# VisualightMicroDIY_036_gnd.net
KiCad netlist of a schematic drawn in EAGLE
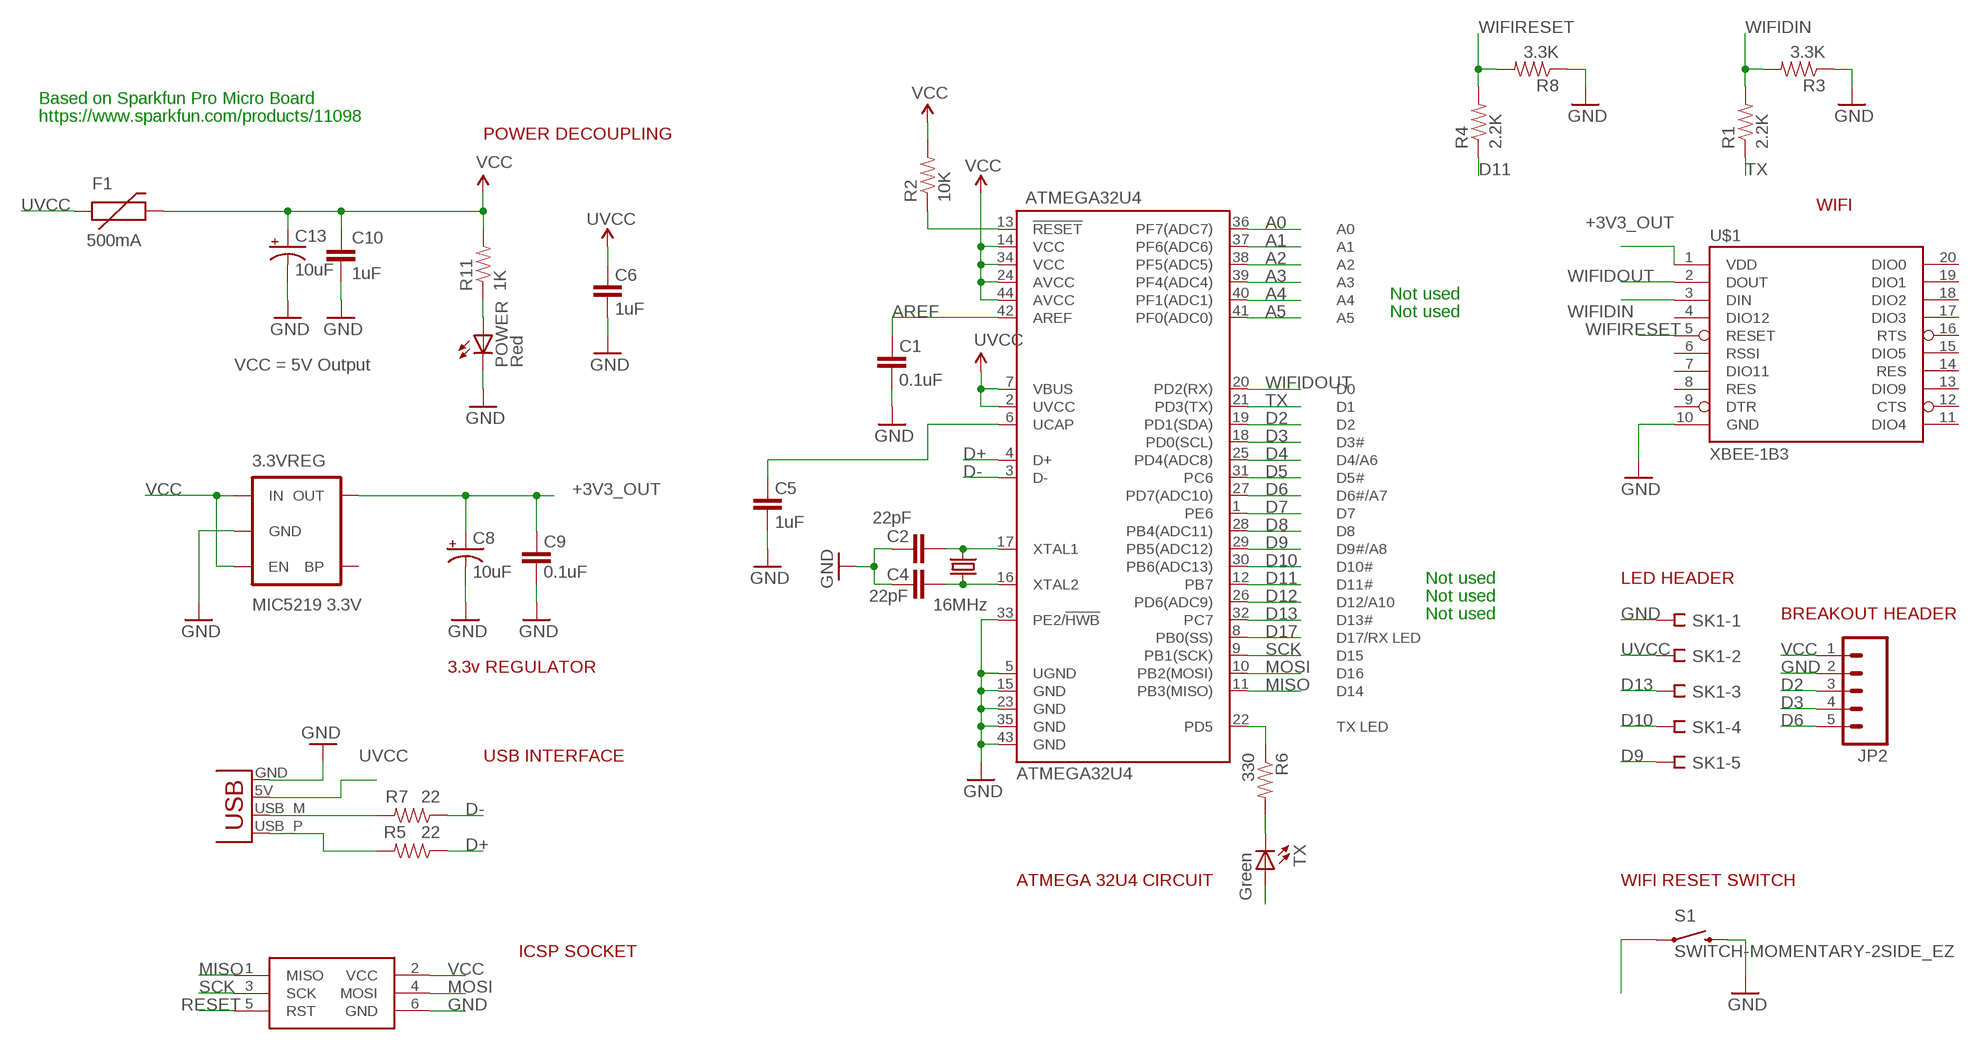
[diagram p0: schematic, sheet 1]

(export (version "E")
  (design (tool "Eeschema 10.0.6"))
  (components
    (comp (ref "3.3VREG")
      (value "MIC5219 3.3V")
      (footprint "eagle-import:SOT23-5")
      (libsource (lib "eagle-import") (part "V_REG_MIC52193.3V"))
    )
    (comp (ref "ATMEGA32U4")
      (value "ATMEGA32U4")
      (footprint "eagle-import:SPARKFUN-DIGITALIC_TQFP44")
      (libsource (lib "eagle-import") (part "ATMEGA32U4TQFP"))
    )
    (comp (ref "C1")
      (value "0.1uF")
      (footprint "eagle-import:0402-CAP")
      (libsource (lib "eagle-import") (part "CAP0402-CAP"))
    )
    (comp (ref "C2")
      (value "22pF")
      (footprint "eagle-import:0402-CAP")
      (libsource (lib "eagle-import") (part "CAP0402-CAP"))
    )
    (comp (ref "C4")
      (value "22pF")
      (footprint "eagle-import:0402-CAP")
      (libsource (lib "eagle-import") (part "CAP0402-CAP"))
    )
    (comp (ref "C5")
      (value "1uF")
      (footprint "eagle-import:0402-CAP")
      (libsource (lib "eagle-import") (part "CAP0402-CAP"))
    )
    (comp (ref "C6")
      (value "1uF")
      (footprint "eagle-import:0402-CAP")
      (libsource (lib "eagle-import") (part "CAP0402-CAP"))
    )
    (comp (ref "C8")
      (value "10uF")
      (footprint "eagle-import:EIA3216")
      (libsource (lib "eagle-import") (part "CAP_POL1206"))
    )
    (comp (ref "C9")
      (value "0.1uF")
      (footprint "eagle-import:0402-CAP")
      (libsource (lib "eagle-import") (part "CAP0402-CAP"))
    )
    (comp (ref "C10")
      (value "1uF")
      (footprint "eagle-import:0402-CAP")
      (libsource (lib "eagle-import") (part "CAP0402-CAP"))
    )
    (comp (ref "C13")
      (value "10uF")
      (footprint "eagle-import:EIA3216")
      (libsource (lib "eagle-import") (part "CAP_POL1206"))
    )
    (comp (ref "F1")
      (value "500mA")
      (footprint "eagle-import:PTC-1206")
      (libsource (lib "eagle-import") (part "PTCSMD"))
    )
    (comp (ref "ISP1")
      (value "AVRISP-6")
      (footprint "eagle-import:AVRISP")
      (libsource (lib "eagle-import") (part "AVRISP-6"))
    )
    (comp (ref "JP2")
      (value "M05PTH")
      (footprint "eagle-import:1X05")
      (libsource (lib "eagle-import") (part "M05PTH"))
    )
    (comp (ref "POWER")
      (value "Red")
      (footprint "eagle-import:LED-0603")
      (libsource (lib "eagle-import") (part "LED0603"))
    )
    (comp (ref "R1")
      (value "2.2K")
      (footprint "eagle-import:0402-RES")
      (libsource (lib "eagle-import") (part "RESISTOR0402-RES"))
    )
    (comp (ref "R2")
      (value "10K")
      (footprint "eagle-import:0402-RES")
      (libsource (lib "eagle-import") (part "RESISTOR0402-RES"))
    )
    (comp (ref "R3")
      (value "3.3K")
      (footprint "eagle-import:0402-RES")
      (libsource (lib "eagle-import") (part "RESISTOR0402-RES"))
    )
    (comp (ref "R4")
      (value "2.2K")
      (footprint "eagle-import:0402-RES")
      (libsource (lib "eagle-import") (part "RESISTOR0402-RES"))
    )
    (comp (ref "R5")
      (value "22")
      (footprint "eagle-import:0402-RES")
      (libsource (lib "eagle-import") (part "RESISTOR0402-RES"))
    )
    (comp (ref "R6")
      (value "330")
      (footprint "eagle-import:0402-RES")
      (libsource (lib "eagle-import") (part "RESISTOR0402-RES"))
    )
    (comp (ref "R7")
      (value "22")
      (footprint "eagle-import:0402-RES")
      (libsource (lib "eagle-import") (part "RESISTOR0402-RES"))
    )
    (comp (ref "R8")
      (value "3.3K")
      (footprint "eagle-import:0402-RES")
      (libsource (lib "eagle-import") (part "RESISTOR0402-RES"))
    )
    (comp (ref "R11")
      (value "1K")
      (footprint "eagle-import:0402-RES")
      (libsource (lib "eagle-import") (part "RESISTOR0402-RES"))
    )
    (comp (ref "S1")
      (value "SWITCH-MOMENTARY-2SIDE_EZ")
      (footprint "eagle-import:TACTILE-PTH-SIDEEZ")
      (libsource (lib "eagle-import") (part "SWITCH-MOMENTARY-2SIDE_EZ"))
    )
    (comp (ref "SK1")
      (value "DF3-05S")
      (footprint "eagle-import:DF3S-05")
      (libsource (lib "eagle-import") (part "DF3-05S"))
    )
    (comp (ref "TX")
      (value "Green")
      (footprint "eagle-import:LED-0603")
      (libsource (lib "eagle-import") (part "LED0603"))
    )
    (comp (ref "U$1")
      (value "XBEE-1B3")
      (footprint "eagle-import:XBEE-SMD")
      (libsource (lib "eagle-import") (part "XBEE-1B3"))
    )
    (comp (ref "X2")
      (value "USBPCB")
      (footprint "eagle-import:USB-A-PCB")
      (libsource (lib "eagle-import") (part "USBPCB"))
    )
    (comp (ref "Y1")
      (value "16MHz")
      (footprint "eagle-import:CRYSTAL-SMD-5X3")
      (libsource (lib "eagle-import") (part "CRYSTAL5X3"))
    )
  )
  (nets
    (net (code "1") (name "/+3V3_OUT") (class "Default")
      (node (ref "3.3VREG") (pin "5") (pinfunction "OUT_5") (pintype "passive"))
      (node (ref "C8") (pin "A") (pinfunction "+_A") (pintype "passive"))
      (node (ref "C9") (pin "2") (pinfunction "2_2") (pintype "passive"))
      (node (ref "U$1") (pin "1") (pinfunction "VDD_1") (pintype "power_in"))
    )
    (net (code "2") (name "/A0") (class "Default")
      (node (ref "ATMEGA32U4") (pin "36") (pinfunction "PF7(ADC7)_36") (pintype "bidirectional"))
    )
    (net (code "3") (name "/A1") (class "Default")
      (node (ref "ATMEGA32U4") (pin "37") (pinfunction "PF6(ADC6)_37") (pintype "bidirectional"))
    )
    (net (code "4") (name "/A2") (class "Default")
      (node (ref "ATMEGA32U4") (pin "38") (pinfunction "PF5(ADC5)_38") (pintype "bidirectional"))
    )
    (net (code "5") (name "/A3") (class "Default")
      (node (ref "ATMEGA32U4") (pin "39") (pinfunction "PF4(ADC4)_39") (pintype "bidirectional"))
    )
    (net (code "6") (name "/A4") (class "Default")
      (node (ref "ATMEGA32U4") (pin "40") (pinfunction "PF1(ADC1)_40") (pintype "bidirectional"))
    )
    (net (code "7") (name "/A5") (class "Default")
      (node (ref "ATMEGA32U4") (pin "41") (pinfunction "PF0(ADC0)_41") (pintype "bidirectional"))
    )
    (net (code "8") (name "/AREF") (class "Default")
      (node (ref "ATMEGA32U4") (pin "42") (pinfunction "AREF_42") (pintype "bidirectional"))
      (node (ref "C1") (pin "2") (pinfunction "2_2") (pintype "passive"))
    )
    (net (code "9") (name "/D+") (class "Default")
      (node (ref "ATMEGA32U4") (pin "4") (pinfunction "D+_4") (pintype "bidirectional"))
      (node (ref "R5") (pin "1") (pinfunction "1_1") (pintype "passive"))
    )
    (net (code "10") (name "/D-") (class "Default")
      (node (ref "ATMEGA32U4") (pin "3") (pinfunction "D-_3") (pintype "bidirectional"))
      (node (ref "R7") (pin "1") (pinfunction "1_1") (pintype "passive"))
    )
    (net (code "11") (name "/D2") (class "Default")
      (node (ref "ATMEGA32U4") (pin "19") (pinfunction "PD1(SDA)_19") (pintype "bidirectional"))
      (node (ref "JP2") (pin "3") (pinfunction "3_3") (pintype "passive"))
    )
    (net (code "12") (name "/D3") (class "Default")
      (node (ref "ATMEGA32U4") (pin "18") (pinfunction "PD0(SCL)_18") (pintype "bidirectional"))
      (node (ref "JP2") (pin "4") (pinfunction "4_4") (pintype "passive"))
    )
    (net (code "13") (name "/D4") (class "Default")
      (node (ref "ATMEGA32U4") (pin "25") (pinfunction "PD4(ADC8)_25") (pintype "bidirectional"))
    )
    (net (code "14") (name "/D5") (class "Default")
      (node (ref "ATMEGA32U4") (pin "31") (pinfunction "PC6_31") (pintype "bidirectional"))
    )
    (net (code "15") (name "/D6") (class "Default")
      (node (ref "ATMEGA32U4") (pin "27") (pinfunction "PD7(ADC10)_27") (pintype "bidirectional"))
      (node (ref "JP2") (pin "5") (pinfunction "5_5") (pintype "passive"))
    )
    (net (code "16") (name "/D7") (class "Default")
      (node (ref "ATMEGA32U4") (pin "1") (pinfunction "PE6_1") (pintype "bidirectional"))
      (node (ref "S1") (pin "1") (pinfunction "1_1") (pintype "passive"))
    )
    (net (code "17") (name "/D8") (class "Default")
      (node (ref "ATMEGA32U4") (pin "28") (pinfunction "PB4(ADC11)_28") (pintype "bidirectional"))
    )
    (net (code "18") (name "/D9") (class "Default")
      (node (ref "ATMEGA32U4") (pin "29") (pinfunction "PB5(ADC12)_29") (pintype "bidirectional"))
      (node (ref "SK1") (pin "5") (pinfunction "S_5") (pintype "passive"))
    )
    (net (code "19") (name "/D10") (class "Default")
      (node (ref "ATMEGA32U4") (pin "30") (pinfunction "PB6(ADC13)_30") (pintype "bidirectional"))
      (node (ref "SK1") (pin "4") (pinfunction "S_4") (pintype "passive"))
    )
    (net (code "20") (name "/D11") (class "Default")
      (node (ref "ATMEGA32U4") (pin "12") (pinfunction "PB7_12") (pintype "bidirectional"))
      (node (ref "R4") (pin "1") (pinfunction "1_1") (pintype "passive"))
    )
    (net (code "21") (name "/D12") (class "Default")
      (node (ref "ATMEGA32U4") (pin "26") (pinfunction "PD6(ADC9)_26") (pintype "bidirectional"))
    )
    (net (code "22") (name "/D13") (class "Default")
      (node (ref "ATMEGA32U4") (pin "32") (pinfunction "PC7_32") (pintype "bidirectional"))
      (node (ref "SK1") (pin "3") (pinfunction "S_3") (pintype "passive"))
    )
    (net (code "23") (name "/D17") (class "Default")
      (node (ref "ATMEGA32U4") (pin "8") (pinfunction "PB0(SS)_8") (pintype "bidirectional"))
    )
    (net (code "24") (name "/MISO") (class "Default")
      (node (ref "ATMEGA32U4") (pin "11") (pinfunction "PB3(MISO)_11") (pintype "bidirectional"))
      (node (ref "ISP1") (pin "1") (pinfunction "MISO_1") (pintype "input"))
    )
    (net (code "25") (name "/MOSI") (class "Default")
      (node (ref "ATMEGA32U4") (pin "10") (pinfunction "PB2(MOSI)_10") (pintype "bidirectional"))
      (node (ref "ISP1") (pin "4") (pinfunction "MOSI_4") (pintype "output"))
    )
    (net (code "26") (name "/RESET") (class "Default")
      (node (ref "ATMEGA32U4") (pin "13") (pinfunction "~{RESET}_13") (pintype "bidirectional"))
      (node (ref "ISP1") (pin "5") (pinfunction "RST_5") (pintype "output"))
      (node (ref "R2") (pin "1") (pinfunction "1_1") (pintype "passive"))
    )
    (net (code "27") (name "/SCK") (class "Default")
      (node (ref "ATMEGA32U4") (pin "9") (pinfunction "PB1(SCK)_9") (pintype "bidirectional"))
      (node (ref "ISP1") (pin "3") (pinfunction "SCK_3") (pintype "output"))
    )
    (net (code "28") (name "/TX") (class "Default")
      (node (ref "ATMEGA32U4") (pin "21") (pinfunction "PD3(TX)_21") (pintype "bidirectional"))
      (node (ref "R1") (pin "1") (pinfunction "1_1") (pintype "passive"))
    )
    (net (code "29") (name "/WIFIDIN") (class "Default")
      (node (ref "R1") (pin "2") (pinfunction "2_2") (pintype "passive"))
      (node (ref "R3") (pin "2") (pinfunction "2_2") (pintype "passive"))
      (node (ref "U$1") (pin "3") (pinfunction "DIN_3") (pintype "input"))
    )
    (net (code "30") (name "/WIFIDOUT") (class "Default")
      (node (ref "ATMEGA32U4") (pin "20") (pinfunction "PD2(RX)_20") (pintype "bidirectional"))
      (node (ref "U$1") (pin "2") (pinfunction "DOUT_2") (pintype "output"))
    )
    (net (code "31") (name "/WIFIRESET") (class "Default")
      (node (ref "R4") (pin "2") (pinfunction "2_2") (pintype "passive"))
      (node (ref "R8") (pin "2") (pinfunction "2_2") (pintype "passive"))
      (node (ref "U$1") (pin "5") (pinfunction "RESET_5") (pintype "input"))
    )
    (net (code "32") (name "GND") (class "Default")
      (node (ref "3.3VREG") (pin "2") (pinfunction "GND_2") (pintype "input"))
      (node (ref "ATMEGA32U4") (pin "15") (pinfunction "GND_15") (pintype "bidirectional"))
      (node (ref "ATMEGA32U4") (pin "23") (pinfunction "GND_23") (pintype "bidirectional"))
      (node (ref "ATMEGA32U4") (pin "33") (pinfunction "PE2/~{HWB}_33") (pintype "bidirectional"))
      (node (ref "ATMEGA32U4") (pin "35") (pinfunction "GND_35") (pintype "bidirectional"))
      (node (ref "ATMEGA32U4") (pin "43") (pinfunction "GND_43") (pintype "bidirectional"))
      (node (ref "ATMEGA32U4") (pin "5") (pinfunction "UGND_5") (pintype "bidirectional"))
      (node (ref "C1") (pin "1") (pinfunction "1_1") (pintype "passive"))
      (node (ref "C10") (pin "2") (pinfunction "2_2") (pintype "passive"))
      (node (ref "C13") (pin "C") (pinfunction "-_C") (pintype "passive"))
      (node (ref "C2") (pin "2") (pinfunction "2_2") (pintype "passive"))
      (node (ref "C4") (pin "2") (pinfunction "2_2") (pintype "passive"))
      (node (ref "C5") (pin "1") (pinfunction "1_1") (pintype "passive"))
      (node (ref "C6") (pin "1") (pinfunction "1_1") (pintype "passive"))
      (node (ref "C8") (pin "C") (pinfunction "-_C") (pintype "passive"))
      (node (ref "C9") (pin "1") (pinfunction "1_1") (pintype "passive"))
      (node (ref "ISP1") (pin "6") (pinfunction "GND_6") (pintype "power_in"))
      (node (ref "JP2") (pin "2") (pinfunction "2_2") (pintype "passive"))
      (node (ref "POWER") (pin "C") (pinfunction "C_C") (pintype "passive"))
      (node (ref "R3") (pin "1") (pinfunction "1_1") (pintype "passive"))
      (node (ref "R8") (pin "1") (pinfunction "1_1") (pintype "passive"))
      (node (ref "S1") (pin "2") (pinfunction "2_2") (pintype "passive"))
      (node (ref "SK1") (pin "1") (pinfunction "S_1") (pintype "passive"))
      (node (ref "U$1") (pin "10") (pinfunction "GND_10") (pintype "power_in"))
      (node (ref "X2") (pin "GND") (pinfunction "GND_GND") (pintype "bidirectional"))
    )
    (net (code "33") (name "Net-(ATMEGA32U4-PD5)") (class "Default")
      (node (ref "ATMEGA32U4") (pin "22") (pinfunction "PD5_22") (pintype "bidirectional"))
      (node (ref "R6") (pin "1") (pinfunction "1_1") (pintype "passive"))
    )
    (net (code "34") (name "Net-(ATMEGA32U4-UCAP)") (class "Default")
      (node (ref "ATMEGA32U4") (pin "6") (pinfunction "UCAP_6") (pintype "bidirectional"))
      (node (ref "C5") (pin "2") (pinfunction "2_2") (pintype "passive"))
    )
    (net (code "35") (name "Net-(ATMEGA32U4-XTAL1)") (class "Default")
      (node (ref "ATMEGA32U4") (pin "17") (pinfunction "XTAL1_17") (pintype "bidirectional"))
      (node (ref "C2") (pin "1") (pinfunction "1_1") (pintype "passive"))
      (node (ref "Y1") (pin "3") (pinfunction "2_3") (pintype "passive"))
    )
    (net (code "36") (name "Net-(ATMEGA32U4-XTAL2)") (class "Default")
      (node (ref "ATMEGA32U4") (pin "16") (pinfunction "XTAL2_16") (pintype "bidirectional"))
      (node (ref "C4") (pin "1") (pinfunction "1_1") (pintype "passive"))
      (node (ref "Y1") (pin "1") (pinfunction "1_1") (pintype "passive"))
    )
    (net (code "37") (name "Net-(POWER-PadA)") (class "Default")
      (node (ref "POWER") (pin "A") (pinfunction "A_A") (pintype "passive"))
      (node (ref "R11") (pin "1") (pinfunction "1_1") (pintype "passive"))
    )
    (net (code "38") (name "Net-(R6-Pad2)") (class "Default")
      (node (ref "R6") (pin "2") (pinfunction "2_2") (pintype "passive"))
      (node (ref "TX") (pin "C") (pinfunction "C_C") (pintype "passive"))
    )
    (net (code "39") (name "Net-(X2-D+)") (class "Default")
      (node (ref "R5") (pin "2") (pinfunction "2_2") (pintype "passive"))
      (node (ref "X2") (pin "USB_P") (pinfunction "D+_USB_P") (pintype "bidirectional"))
    )
    (net (code "40") (name "Net-(X2-D-)") (class "Default")
      (node (ref "R7") (pin "2") (pinfunction "2_2") (pintype "passive"))
      (node (ref "X2") (pin "USB_M") (pinfunction "D-_USB_M") (pintype "bidirectional"))
    )
    (net (code "41") (name "UVCC") (class "Default")
      (node (ref "ATMEGA32U4") (pin "2") (pinfunction "UVCC_2") (pintype "bidirectional"))
      (node (ref "ATMEGA32U4") (pin "7") (pinfunction "VBUS_7") (pintype "bidirectional"))
      (node (ref "C6") (pin "2") (pinfunction "2_2") (pintype "passive"))
      (node (ref "F1") (pin "1") (pinfunction "1_1") (pintype "bidirectional"))
      (node (ref "SK1") (pin "2") (pinfunction "S_2") (pintype "passive"))
      (node (ref "X2") (pin "5V") (pinfunction "VBUS_5V") (pintype "bidirectional"))
    )
    (net (code "42") (name "VCC") (class "Default")
      (node (ref "3.3VREG") (pin "1") (pinfunction "IN_1") (pintype "input"))
      (node (ref "3.3VREG") (pin "3") (pinfunction "EN_3") (pintype "input"))
      (node (ref "ATMEGA32U4") (pin "14") (pinfunction "VCC_14") (pintype "bidirectional"))
      (node (ref "ATMEGA32U4") (pin "24") (pinfunction "AVCC_24") (pintype "bidirectional"))
      (node (ref "ATMEGA32U4") (pin "34") (pinfunction "VCC_34") (pintype "bidirectional"))
      (node (ref "ATMEGA32U4") (pin "44") (pinfunction "AVCC_44") (pintype "bidirectional"))
      (node (ref "C10") (pin "1") (pinfunction "1_1") (pintype "passive"))
      (node (ref "C13") (pin "A") (pinfunction "+_A") (pintype "passive"))
      (node (ref "F1") (pin "2") (pinfunction "2_2") (pintype "bidirectional"))
      (node (ref "ISP1") (pin "2") (pinfunction "VCC_2") (pintype "power_in"))
      (node (ref "JP2") (pin "1") (pinfunction "1_1") (pintype "passive"))
      (node (ref "R11") (pin "2") (pinfunction "2_2") (pintype "passive"))
      (node (ref "R2") (pin "2") (pinfunction "2_2") (pintype "passive"))
      (node (ref "TX") (pin "A") (pinfunction "A_A") (pintype "passive"))
    )
    (net (code "43") (name "unconnected-(3.3VREG-BP-Pad4)") (class "Default")
      (node (ref "3.3VREG") (pin "4") (pinfunction "BP_4") (pintype "input"))
    )
    (net (code "44") (name "unconnected-(U$1-CTS-Pad12)") (class "Default")
      (node (ref "U$1") (pin "12") (pinfunction "CTS_12") (pintype "output"))
    )
    (net (code "45") (name "unconnected-(U$1-DIO0-Pad20)") (class "Default")
      (node (ref "U$1") (pin "20") (pinfunction "DIO0_20") (pintype "bidirectional"))
    )
    (net (code "46") (name "unconnected-(U$1-DIO1-Pad19)") (class "Default")
      (node (ref "U$1") (pin "19") (pinfunction "DIO1_19") (pintype "bidirectional"))
    )
    (net (code "47") (name "unconnected-(U$1-DIO2-Pad18)") (class "Default")
      (node (ref "U$1") (pin "18") (pinfunction "DIO2_18") (pintype "bidirectional"))
    )
    (net (code "48") (name "unconnected-(U$1-DIO3-Pad17)") (class "Default")
      (node (ref "U$1") (pin "17") (pinfunction "DIO3_17") (pintype "bidirectional"))
    )
    (net (code "49") (name "unconnected-(U$1-DIO4-Pad11)") (class "Default")
      (node (ref "U$1") (pin "11") (pinfunction "DIO4_11") (pintype "bidirectional"))
    )
    (net (code "50") (name "unconnected-(U$1-DIO5-Pad15)") (class "Default")
      (node (ref "U$1") (pin "15") (pinfunction "DIO5_15") (pintype "bidirectional"))
    )
    (net (code "51") (name "unconnected-(U$1-DIO9-Pad13)") (class "Default")
      (node (ref "U$1") (pin "13") (pinfunction "DIO9_13") (pintype "bidirectional"))
    )
    (net (code "52") (name "unconnected-(U$1-DIO11-Pad7)") (class "Default")
      (node (ref "U$1") (pin "7") (pinfunction "DIO11_7") (pintype "bidirectional"))
    )
    (net (code "53") (name "unconnected-(U$1-DIO12-Pad4)") (class "Default")
      (node (ref "U$1") (pin "4") (pinfunction "DIO12_4") (pintype "bidirectional"))
    )
    (net (code "54") (name "unconnected-(U$1-DTR-Pad9)") (class "Default")
      (node (ref "U$1") (pin "9") (pinfunction "DTR_9") (pintype "bidirectional"))
    )
    (net (code "55") (name "unconnected-(U$1-RES-Pad8)") (class "Default")
      (node (ref "U$1") (pin "8") (pinfunction "RES_8") (pintype "bidirectional"))
    )
    (net (code "56") (name "unconnected-(U$1-RES-Pad14)") (class "Default")
      (node (ref "U$1") (pin "14") (pinfunction "RES_14") (pintype "bidirectional"))
    )
    (net (code "57") (name "unconnected-(U$1-RSSI-Pad6)") (class "Default")
      (node (ref "U$1") (pin "6") (pinfunction "RSSI_6") (pintype "bidirectional"))
    )
    (net (code "58") (name "unconnected-(U$1-RTS-Pad16)") (class "Default")
      (node (ref "U$1") (pin "16") (pinfunction "RTS_16") (pintype "input"))
    )
  )
)
